# speedPulserPro.net
KiCad netlist of a schematic drawn in EasyEDA Pro
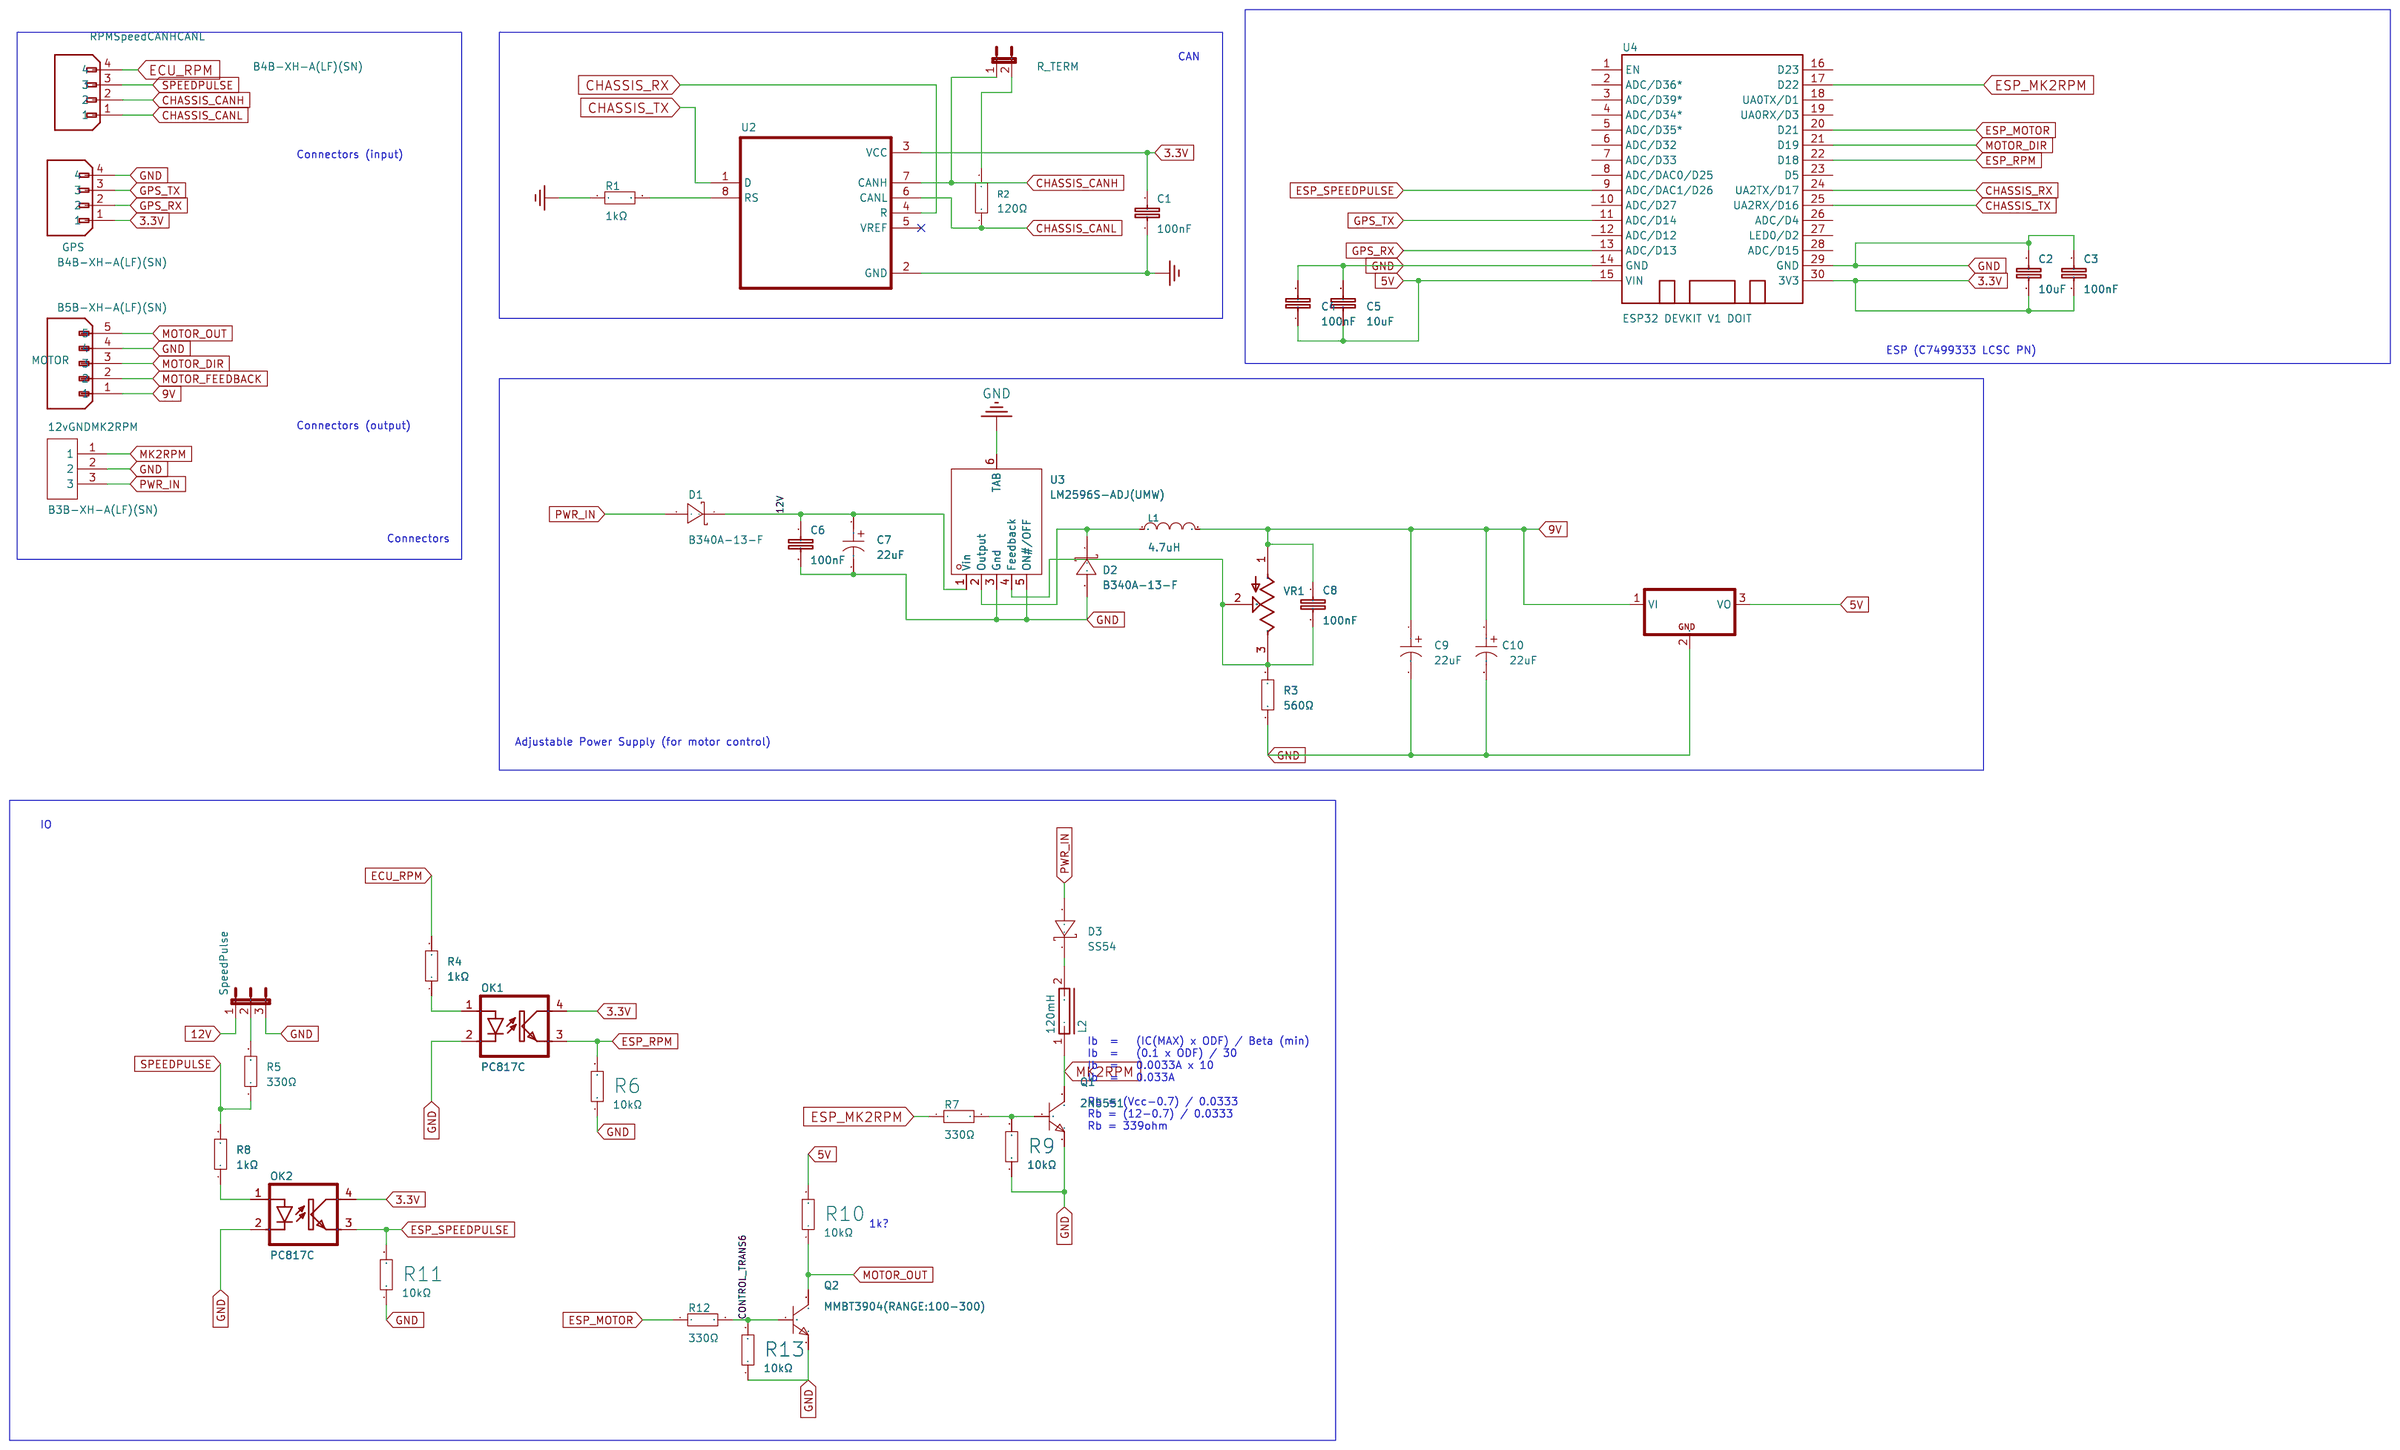
[diagram p0: schematic sheet]

(export (version "E")
  (design (tool "Eeschema 10.0.6"))
  (components
    (comp (ref "12vGNDMK2RPM")
      (value "B3B-XH-A(LF)(SN)")
      (footprint "easyedapro:CONN-TH_3P-P2.50_A2501WV2-3P")
      (fields (field (name "Manufacturer") "JST"))
      (libsource (lib "easyedapro") (part "B3B-XH-A(LF)(SN)"))
    )
    (comp (ref "C1")
      (value "100nF")
      (description "Capacitance:100nF Tolerance:±10% Tolerance:±10% Voltage Rating:50V Temperature Coefficient:X7R")
      (fields
        (field (name "Manufacturer Part") "CC0603KRX7R9BB104")
        (field (name "Manufacturer") "YAGEO(国巨)")
      )
      (libsource (lib "easyedapro") (part "capacitor-wima_C_2.5/2"))
    )
    (comp (ref "C2")
      (value "10uF")
      (fields
        (field (name "Manufacturer Part") "CL21A106KAYNNNE")
        (field (name "Manufacturer") "SAMSUNG(三星)")
      )
      (libsource (lib "easyedapro") (part "capacitor-wima_C_2.5/2"))
    )
    (comp (ref "C3")
      (value "100nF")
      (description "Capacitance:100nF Tolerance:±10% Tolerance:±10% Voltage Rating:50V Temperature Coefficient:X7R")
      (fields
        (field (name "Manufacturer Part") "CC0603KRX7R9BB104")
        (field (name "Manufacturer") "YAGEO(国巨)")
      )
      (libsource (lib "easyedapro") (part "capacitor-wima_C_2.5/2"))
    )
    (comp (ref "C4")
      (value "100nF")
      (description "Capacitance:100nF Tolerance:±10% Tolerance:±10% Voltage Rating:50V Temperature Coefficient:X7R")
      (fields
        (field (name "Manufacturer Part") "CC0603KRX7R9BB104")
        (field (name "Manufacturer") "YAGEO(国巨)")
      )
      (libsource (lib "easyedapro") (part "capacitor-wima_C_2.5/2"))
    )
    (comp (ref "C5")
      (value "10uF")
      (fields
        (field (name "Manufacturer Part") "CL21A106KAYNNNE")
        (field (name "Manufacturer") "SAMSUNG(三星)")
      )
      (libsource (lib "easyedapro") (part "capacitor-wima_C_2.5/2"))
    )
    (comp (ref "C6")
      (value "100nF")
      (description "Capacitance:100nF Tolerance:±10% Tolerance:±10% Voltage Rating:50V Temperature Coefficient:-")
      (fields
        (field (name "Manufacturer Part") "CT41G-0805-2X1-50V-0.1μF-K(N)")
        (field (name "Manufacturer") "TORCH(火炬)")
      )
      (libsource (lib "easyedapro") (part "capacitor-wima_C_2.5/2"))
    )
    (comp (ref "C7")
      (value "22uF")
      (footprint "easyedapro:CAP-SMD_BD5.0-L5.3-W5.3-LS6.3-FD-1")
      (fields (field (name "Manufacturer Part") "RST22UF35V025") (field (name "Manufacturer") "KNSCHA(科尼盛)"))
      (libsource (lib "easyedapro") (part "RST22UF35V025"))
    )
    (comp (ref "C8")
      (value "100nF")
      (description "Capacitance:100nF Tolerance:±10% Tolerance:±10% Voltage Rating:50V Temperature Coefficient:-")
      (fields
        (field (name "Manufacturer Part") "CT41G-0805-2X1-50V-0.1μF-K(N)")
        (field (name "Manufacturer") "TORCH(火炬)")
      )
      (libsource (lib "easyedapro") (part "capacitor-wima_C_2.5/2"))
    )
    (comp (ref "C9")
      (value "22uF")
      (footprint "easyedapro:CAP-SMD_BD5.0-L5.3-W5.3-LS6.3-FD-1")
      (fields (field (name "Manufacturer Part") "RST22UF35V025") (field (name "Manufacturer") "KNSCHA(科尼盛)"))
      (libsource (lib "easyedapro") (part "RST22UF35V025"))
    )
    (comp (ref "C10")
      (value "22uF")
      (footprint "easyedapro:CAP-SMD_BD5.0-L5.3-W5.3-LS6.3-FD-1")
      (fields (field (name "Manufacturer Part") "RST22UF35V025") (field (name "Manufacturer") "KNSCHA(科尼盛)"))
      (libsource (lib "easyedapro") (part "RST22UF35V025"))
    )
    (comp (ref "D1")
      (value "B340A-13-F")
      (footprint "easyedapro:SMA_L4.4-W2.6-LS5.0-RD")
      (fields (field (name "Manufacturer") "DIODES(美台)"))
      (libsource (lib "easyedapro") (part "B340A-13-F"))
    )
    (comp (ref "D2")
      (value "B340A-13-F")
      (footprint "easyedapro:SMA_L4.4-W2.6-LS5.0-RD")
      (fields (field (name "Manufacturer") "DIODES(美台)"))
      (libsource (lib "easyedapro") (part "B340A-13-F"))
    )
    (comp (ref "D3")
      (value "SS54")
      (footprint "easyedapro:SMA_L4.4-W2.8-LS5.4-R-RD")
      (fields (field (name "Manufacturer") "MDD(辰达半导体)"))
      (libsource (lib "easyedapro") (part "SS54_C22452"))
    )
    (comp (ref "GPS")
      (value "B4B-XH-A(LF)(SN)")
      (fields (field (name "Manufacturer") "JST"))
      (libsource (lib "easyedapro") (part "B4B-XH-A_LF__SN__B4B-XH-A(LF)(SN)_"))
    )
    (comp (ref "IC1")
      (value "L7805ABD2T-TR")
      (fields (field (name "Manufacturer") "ST(意法半导体)"))
      (libsource (lib "easyedapro") (part "linear_78*_TV"))
    )
    (comp (ref "L1")
      (value "4.7uH")
      (footprint "easyedapro:IND-SMD_L4.8-W4.5")
      (fields (field (name "Manufacturer Part") "SMMS0420-4R7M") (field (name "Manufacturer") "SXN(顺翔诺)"))
      (libsource (lib "easyedapro") (part "SMMS0420-4R7M"))
    )
    (comp (ref "L2")
      (value "120mH")
      (fields (field (name "Manufacturer Part") "DR125-124-R") (field (name "Manufacturer") "EATON(伊顿)"))
      (libsource (lib "easyedapro") (part "DR125_DR125_"))
    )
    (comp (ref "MOTOR")
      (value "B5B-XH-A(LF)(SN)")
      (fields (field (name "Manufacturer") "JST"))
      (libsource (lib "easyedapro") (part "B5B-XH-A_LF__SN__B5B-XH-A(LF)(SN)_"))
    )
    (comp (ref "OK1")
      (value "PC817C")
      (fields (field (name "Manufacturer") "GOODWORK(固得沃克)"))
      (libsource (lib "easyedapro") (part "optocoupler_PC817_"))
    )
    (comp (ref "OK2")
      (value "PC817C")
      (fields (field (name "Manufacturer") "GOODWORK(固得沃克)"))
      (libsource (lib "easyedapro") (part "optocoupler_PC817_"))
    )
    (comp (ref "Q1")
      (value "2N5551")
      (footprint "easyedapro:SOT-23-3_L2.9-W1.4-P1.90-LS2.5-BR")
      (fields (field (name "Manufacturer") "RUILON(瑞隆源)"))
      (libsource (lib "easyedapro") (part "2N5551_C7529570"))
    )
    (comp (ref "Q2")
      (value "MMBT3904(RANGE:100-300)")
      (footprint "easyedapro:SOT-23-3_L2.9-W1.3-P1.90-LS2.4-BR")
      (fields (field (name "Manufacturer") "CJ(江苏长电/长晶)"))
      (libsource (lib "easyedapro") (part "MMBT3904"))
    )
    (comp (ref "R1")
      (value "1kΩ")
      (footprint "easyedapro:R0603")
      (fields
        (field (name "Manufacturer Part") "0603WAF1001T5E")
        (field (name "Manufacturer") "UNI-ROYAL(厚声)")
      )
      (libsource (lib "easyedapro") (part "0603WAF1001T5E"))
    )
    (comp (ref "R2")
      (value "120Ω")
      (footprint "easyedapro:R0603")
      (fields
        (field (name "Manufacturer Part") "0603WAF1200T5E")
        (field (name "Manufacturer") "UNI-ROYAL(厚声)")
      )
      (libsource (lib "easyedapro") (part "0603WAF1200T5E"))
    )
    (comp (ref "R3")
      (value "560Ω")
      (footprint "easyedapro:R0603")
      (fields
        (field (name "Manufacturer Part") "0603WAF5600T5E")
        (field (name "Manufacturer") "UNI-ROYAL(厚声)")
      )
      (libsource (lib "easyedapro") (part "0603WAF5600T5E"))
    )
    (comp (ref "R4")
      (value "1kΩ")
      (footprint "easyedapro:R0603")
      (fields
        (field (name "Manufacturer Part") "0603WAF1001T5E")
        (field (name "Manufacturer") "UNI-ROYAL(厚声)")
      )
      (libsource (lib "easyedapro") (part "0603WAF1001T5E"))
    )
    (comp (ref "R5")
      (value "330Ω")
      (footprint "easyedapro:R0603")
      (fields
        (field (name "Manufacturer Part") "0603WAF3300T5E")
        (field (name "Manufacturer") "UNI-ROYAL(厚声)")
      )
      (libsource (lib "easyedapro") (part "0603WAF3300T5E"))
    )
    (comp (ref "R6")
      (value "10kΩ")
      (footprint "easyedapro:R0603")
      (fields
        (field (name "Manufacturer Part") "0603WAF1002T5E")
        (field (name "Manufacturer") "UNI-ROYAL(厚声)")
      )
      (libsource (lib "easyedapro") (part "0603WAF1002T5E"))
    )
    (comp (ref "R7")
      (value "330Ω")
      (footprint "easyedapro:R0603")
      (fields
        (field (name "Manufacturer Part") "0603WAF3300T5E")
        (field (name "Manufacturer") "UNI-ROYAL(厚声)")
      )
      (libsource (lib "easyedapro") (part "0603WAF3300T5E"))
    )
    (comp (ref "R8")
      (value "1kΩ")
      (footprint "easyedapro:R0603")
      (fields
        (field (name "Manufacturer Part") "0603WAF1001T5E")
        (field (name "Manufacturer") "UNI-ROYAL(厚声)")
      )
      (libsource (lib "easyedapro") (part "0603WAF1001T5E"))
    )
    (comp (ref "R9")
      (value "10kΩ")
      (footprint "easyedapro:R0603")
      (fields
        (field (name "Manufacturer Part") "0603WAF1002T5E")
        (field (name "Manufacturer") "UNI-ROYAL(厚声)")
      )
      (libsource (lib "easyedapro") (part "0603WAF1002T5E"))
    )
    (comp (ref "R10")
      (value "10kΩ")
      (footprint "easyedapro:R0603")
      (fields
        (field (name "Manufacturer Part") "0603WAF1002T5E")
        (field (name "Manufacturer") "UNI-ROYAL(厚声)")
      )
      (libsource (lib "easyedapro") (part "0603WAF1002T5E"))
    )
    (comp (ref "R11")
      (value "10kΩ")
      (footprint "easyedapro:R0603")
      (fields
        (field (name "Manufacturer Part") "0603WAF1002T5E")
        (field (name "Manufacturer") "UNI-ROYAL(厚声)")
      )
      (libsource (lib "easyedapro") (part "0603WAF1002T5E"))
    )
    (comp (ref "R12")
      (value "330Ω")
      (footprint "easyedapro:R0603")
      (fields
        (field (name "Manufacturer Part") "0603WAF3300T5E")
        (field (name "Manufacturer") "UNI-ROYAL(厚声)")
      )
      (libsource (lib "easyedapro") (part "0603WAF3300T5E"))
    )
    (comp (ref "R13")
      (value "10kΩ")
      (footprint "easyedapro:R0603")
      (fields
        (field (name "Manufacturer Part") "0603WAF1002T5E")
        (field (name "Manufacturer") "UNI-ROYAL(厚声)")
      )
      (libsource (lib "easyedapro") (part "0603WAF1002T5E"))
    )
    (comp (ref "RPMSpeedCANHCANL")
      (value "B4B-XH-A(LF)(SN)")
      (fields (field (name "Manufacturer") "JST"))
      (libsource (lib "easyedapro") (part "B4B-XH-A_LF__SN__B4B-XH-A(LF)(SN)_"))
    )
    (comp (ref "R_TERM")
      (value "PZ254V-11-02P")
      (fields (field (name "Manufacturer") "XFCN(兴飞)"))
      (libsource (lib "easyedapro") (part "jumper_JP1E_"))
    )
    (comp (ref "SpeedPulse")
      (value "PZ254V-11-03P")
      (fields (field (name "Manufacturer") "XFCN(兴飞)"))
      (libsource (lib "easyedapro") (part "jumper_JP2E_"))
    )
    (comp (ref "U2")
      (value "SN65HVD230DR")
      (fields (field (name "Manufacturer") "TI(德州仪器)"))
      (libsource (lib "easyedapro") (part "SN65HVD230DR_SN65HVD230DR_"))
    )
    (comp (ref "U3")
      (value "LM2596S-ADJ(UMW)")
      (footprint "easyedapro:TO-263-5_L10.2-W8.9-P1.70-BR")
      (fields (field (name "Manufacturer") "UMW(友台半导体)"))
      (libsource (lib "easyedapro") (part "LM2596S-ADJ"))
    )
    (comp (ref "U4")
      (value "ESP32 DEVKIT V1 DOIT")
      (footprint "easyedapro:DOIT-ESP32-DEVKIT-V1")
      (libsource (lib "easyedapro") (part "ESP32 DEVKIT V1 DOIT"))
    )
    (comp (ref "VR1")
      (value "10kΩ")
      (description "Resistance: Tolerance:±10% Tolerance:±10%")
      (fields (field (name "Manufacturer Part") "3362P-1-103") (field (name "Manufacturer") "BOCHEN(博晨)"))
      (libsource (lib "easyedapro") (part "3362P-1-253LF_3362P-1-253LF_"))
    )
  )
  (nets
    (net (code "1") (name "/CONTROL_TRANS6") (class "Default")
      (node (ref "Q2") (pin "1") (pinfunction "B_1") (pintype "unspecified"))
      (node (ref "R12") (pin "2") (pinfunction "2_2") (pintype "input"))
      (node (ref "R13") (pin "2") (pinfunction "2_2") (pintype "input"))
    )
    (net (code "2") (name "3.3V") (class "Default")
      (node (ref "C1") (pin "1") (pinfunction "1_1") (pintype "unspecified"))
      (node (ref "C2") (pin "2") (pinfunction "2_2") (pintype "unspecified"))
      (node (ref "C3") (pin "2") (pinfunction "2_2") (pintype "unspecified"))
      (node (ref "GPS") (pin "1") (pinfunction "1_1") (pintype "unspecified"))
      (node (ref "OK1") (pin "4") (pinfunction "COL_4") (pintype "unspecified"))
      (node (ref "OK2") (pin "4") (pinfunction "COL_4") (pintype "unspecified"))
      (node (ref "U2") (pin "3") (pinfunction "VCC_3") (pintype "unspecified"))
      (node (ref "U4") (pin "30") (pinfunction "3V3_30") (pintype "bidirectional"))
    )
    (net (code "3") (name "5V") (class "Default")
      (node (ref "C4") (pin "1") (pinfunction "1_1") (pintype "unspecified"))
      (node (ref "C5") (pin "1") (pinfunction "1_1") (pintype "unspecified"))
      (node (ref "IC1") (pin "3") (pinfunction "VO_3") (pintype "unspecified"))
      (node (ref "R10") (pin "2") (pinfunction "2_2") (pintype "input"))
      (node (ref "U4") (pin "15") (pinfunction "VIN_15") (pintype "input"))
    )
    (net (code "4") (name "9V") (class "Default")
      (node (ref "C10") (pin "1") (pinfunction "1_1") (pintype "input"))
      (node (ref "C8") (pin "1") (pinfunction "1_1") (pintype "unspecified"))
      (node (ref "C9") (pin "1") (pinfunction "1_1") (pintype "input"))
      (node (ref "IC1") (pin "1") (pinfunction "VI_1") (pintype "input"))
      (node (ref "L1") (pin "2") (pinfunction "2_2") (pintype "input"))
      (node (ref "MOTOR") (pin "1") (pinfunction "1_1") (pintype "unspecified"))
      (node (ref "VR1") (pin "1") (pinfunction "CCW_1") (pintype "unspecified"))
    )
    (net (code "5") (name "12V") (class "Default")
      (node (ref "C6") (pin "1") (pinfunction "1_1") (pintype "unspecified"))
      (node (ref "C7") (pin "1") (pinfunction "1_1") (pintype "input"))
      (node (ref "D1") (pin "1") (pinfunction "K_1") (pintype "unspecified"))
      (node (ref "SpeedPulse") (pin "1") (pinfunction "1_1") (pintype "unspecified"))
      (node (ref "U3") (pin "1") (pinfunction "Vin_1") (pintype "unspecified"))
    )
    (net (code "6") (name "CHASSIS_CANH") (class "Default")
      (node (ref "RPMSpeedCANHCANL") (pin "2") (pinfunction "2_2") (pintype "unspecified"))
      (node (ref "R_TERM") (pin "1") (pinfunction "1_1") (pintype "unspecified"))
      (node (ref "U2") (pin "7") (pinfunction "CANH_7") (pintype "output"))
    )
    (net (code "7") (name "CHASSIS_CANL") (class "Default")
      (node (ref "R2") (pin "1") (pinfunction "1_1") (pintype "input"))
      (node (ref "RPMSpeedCANHCANL") (pin "1") (pinfunction "1_1") (pintype "unspecified"))
      (node (ref "U2") (pin "6") (pinfunction "CANL_6") (pintype "output"))
    )
    (net (code "8") (name "CHASSIS_RX") (class "Default")
      (node (ref "U2") (pin "4") (pinfunction "R_4") (pintype "output"))
      (node (ref "U4") (pin "24") (pinfunction "UA2TX/D17_24") (pintype "bidirectional"))
    )
    (net (code "9") (name "CHASSIS_TX") (class "Default")
      (node (ref "U2") (pin "1") (pinfunction "D_1") (pintype "input"))
      (node (ref "U4") (pin "25") (pinfunction "UA2RX/D16_25") (pintype "bidirectional"))
    )
    (net (code "10") (name "ECU_RPM") (class "Default")
      (node (ref "R4") (pin "2") (pinfunction "2_2") (pintype "input"))
      (node (ref "RPMSpeedCANHCANL") (pin "4") (pinfunction "4_4") (pintype "unspecified"))
    )
    (net (code "11") (name "ESP_MK2RPM") (class "Default")
      (node (ref "R7") (pin "1") (pinfunction "1_1") (pintype "input"))
      (node (ref "U4") (pin "17") (pinfunction "D22_17") (pintype "bidirectional"))
    )
    (net (code "12") (name "ESP_MOTOR") (class "Default")
      (node (ref "R12") (pin "1") (pinfunction "1_1") (pintype "input"))
      (node (ref "U4") (pin "20") (pinfunction "D21_20") (pintype "bidirectional"))
    )
    (net (code "13") (name "ESP_RPM") (class "Default")
      (node (ref "OK1") (pin "3") (pinfunction "EMIT_3") (pintype "unspecified"))
      (node (ref "R6") (pin "2") (pinfunction "2_2") (pintype "input"))
      (node (ref "U4") (pin "22") (pinfunction "D18_22") (pintype "bidirectional"))
    )
    (net (code "14") (name "ESP_SPEEDPULSE") (class "Default")
      (node (ref "OK2") (pin "3") (pinfunction "EMIT_3") (pintype "unspecified"))
      (node (ref "R11") (pin "2") (pinfunction "2_2") (pintype "input"))
      (node (ref "U4") (pin "9") (pinfunction "ADC/DAC1/D26_9") (pintype "bidirectional"))
    )
    (net (code "15") (name "GND") (class "Default")
      (node (ref "12vGNDMK2RPM") (pin "2") (pinfunction "2_2") (pintype "unspecified"))
      (node (ref "C1") (pin "2") (pinfunction "2_2") (pintype "unspecified"))
      (node (ref "C10") (pin "2") (pinfunction "2_2") (pintype "input"))
      (node (ref "C2") (pin "1") (pinfunction "1_1") (pintype "unspecified"))
      (node (ref "C3") (pin "1") (pinfunction "1_1") (pintype "unspecified"))
      (node (ref "C4") (pin "2") (pinfunction "2_2") (pintype "unspecified"))
      (node (ref "C5") (pin "2") (pinfunction "2_2") (pintype "unspecified"))
      (node (ref "C6") (pin "2") (pinfunction "2_2") (pintype "unspecified"))
      (node (ref "C7") (pin "2") (pinfunction "2_2") (pintype "input"))
      (node (ref "C9") (pin "2") (pinfunction "2_2") (pintype "input"))
      (node (ref "D2") (pin "2") (pinfunction "A_2") (pintype "unspecified"))
      (node (ref "GPS") (pin "4") (pinfunction "4_4") (pintype "unspecified"))
      (node (ref "IC1") (pin "2") (pinfunction "GND_2") (pintype "unspecified"))
      (node (ref "MOTOR") (pin "4") (pinfunction "4_4") (pintype "unspecified"))
      (node (ref "OK1") (pin "2") (pinfunction "C_2") (pintype "unspecified"))
      (node (ref "OK2") (pin "2") (pinfunction "C_2") (pintype "unspecified"))
      (node (ref "Q1") (pin "2") (pinfunction "E_2") (pintype "unspecified"))
      (node (ref "Q2") (pin "2") (pinfunction "E_2") (pintype "unspecified"))
      (node (ref "R1") (pin "1") (pinfunction "1_1") (pintype "input"))
      (node (ref "R11") (pin "1") (pinfunction "1_1") (pintype "input"))
      (node (ref "R13") (pin "1") (pinfunction "1_1") (pintype "input"))
      (node (ref "R3") (pin "1") (pinfunction "1_1") (pintype "input"))
      (node (ref "R6") (pin "1") (pinfunction "1_1") (pintype "input"))
      (node (ref "R9") (pin "1") (pinfunction "1_1") (pintype "input"))
      (node (ref "SpeedPulse") (pin "3") (pinfunction "3_3") (pintype "unspecified"))
      (node (ref "U2") (pin "2") (pinfunction "GND_2") (pintype "unspecified"))
      (node (ref "U3") (pin "3") (pinfunction "Gnd_3") (pintype "unspecified"))
      (node (ref "U3") (pin "5") (pinfunction "ON#/OFF_5") (pintype "unspecified"))
      (node (ref "U3") (pin "6") (pinfunction "TAB_6") (pintype "unspecified"))
      (node (ref "U4") (pin "14") (pinfunction "GND_14") (pintype "bidirectional"))
      (node (ref "U4") (pin "29") (pinfunction "GND_29") (pintype "bidirectional"))
    )
    (net (code "16") (name "GPS_RX") (class "Default")
      (node (ref "GPS") (pin "2") (pinfunction "2_2") (pintype "unspecified"))
      (node (ref "U4") (pin "13") (pinfunction "ADC/D13_13") (pintype "bidirectional"))
    )
    (net (code "17") (name "GPS_TX") (class "Default")
      (node (ref "GPS") (pin "3") (pinfunction "3_3") (pintype "unspecified"))
      (node (ref "U4") (pin "11") (pinfunction "ADC/D14_11") (pintype "bidirectional"))
    )
    (net (code "18") (name "MK2RPM") (class "Default")
      (node (ref "12vGNDMK2RPM") (pin "1") (pinfunction "1_1") (pintype "unspecified"))
      (node (ref "L2") (pin "1") (pinfunction "1_1") (pintype "unspecified"))
      (node (ref "Q1") (pin "3") (pinfunction "C_3") (pintype "unspecified"))
    )
    (net (code "19") (name "MOTOR_DIR") (class "Default")
      (node (ref "MOTOR") (pin "3") (pinfunction "3_3") (pintype "unspecified"))
      (node (ref "U4") (pin "21") (pinfunction "D19_21") (pintype "bidirectional"))
    )
    (net (code "20") (name "MOTOR_FEEDBACK") (class "Default")
      (node (ref "MOTOR") (pin "2") (pinfunction "2_2") (pintype "unspecified"))
    )
    (net (code "21") (name "MOTOR_OUT") (class "Default")
      (node (ref "MOTOR") (pin "5") (pinfunction "5_5") (pintype "unspecified"))
      (node (ref "Q2") (pin "3") (pinfunction "C_3") (pintype "unspecified"))
      (node (ref "R10") (pin "1") (pinfunction "1_1") (pintype "input"))
    )
    (net (code "22") (name "Net-(D2-K)") (class "Default")
      (node (ref "D2") (pin "1") (pinfunction "K_1") (pintype "unspecified"))
      (node (ref "L1") (pin "1") (pinfunction "1_1") (pintype "input"))
      (node (ref "U3") (pin "2") (pinfunction "Output_2") (pintype "unspecified"))
    )
    (net (code "23") (name "Net-(D3-K)") (class "Default")
      (node (ref "D3") (pin "2") (pinfunction "K_2") (pintype "unspecified"))
      (node (ref "L2") (pin "2") (pinfunction "2_2") (pintype "unspecified"))
    )
    (net (code "24") (name "Net-(OK1-A)") (class "Default")
      (node (ref "OK1") (pin "1") (pinfunction "A_1") (pintype "unspecified"))
      (node (ref "R4") (pin "1") (pinfunction "1_1") (pintype "input"))
    )
    (net (code "25") (name "Net-(OK2-A)") (class "Default")
      (node (ref "OK2") (pin "1") (pinfunction "A_1") (pintype "unspecified"))
      (node (ref "R8") (pin "1") (pinfunction "1_1") (pintype "input"))
    )
    (net (code "26") (name "Net-(Q1-B)") (class "Default")
      (node (ref "Q1") (pin "1") (pinfunction "B_1") (pintype "unspecified"))
      (node (ref "R7") (pin "2") (pinfunction "2_2") (pintype "input"))
      (node (ref "R9") (pin "2") (pinfunction "2_2") (pintype "input"))
    )
    (net (code "27") (name "Net-(R2-Pad2)") (class "Default")
      (node (ref "R2") (pin "2") (pinfunction "2_2") (pintype "input"))
      (node (ref "R_TERM") (pin "2") (pinfunction "2_2") (pintype "unspecified"))
    )
    (net (code "28") (name "Net-(R5-Pad2)") (class "Default")
      (node (ref "R5") (pin "2") (pinfunction "2_2") (pintype "input"))
      (node (ref "SpeedPulse") (pin "2") (pinfunction "2_2") (pintype "unspecified"))
    )
    (net (code "29") (name "Net-(U2-RS)") (class "Default")
      (node (ref "R1") (pin "2") (pinfunction "2_2") (pintype "input"))
      (node (ref "U2") (pin "8") (pinfunction "RS_8") (pintype "input"))
    )
    (net (code "30") (name "Net-(U3-Feedback)") (class "Default")
      (node (ref "C8") (pin "2") (pinfunction "2_2") (pintype "unspecified"))
      (node (ref "R3") (pin "2") (pinfunction "2_2") (pintype "input"))
      (node (ref "U3") (pin "4") (pinfunction "Feedback_4") (pintype "unspecified"))
      (node (ref "VR1") (pin "2") (pinfunction "WIPER_2") (pintype "unspecified"))
      (node (ref "VR1") (pin "3") (pinfunction "CW_3") (pintype "unspecified"))
    )
    (net (code "31") (name "PWR_IN") (class "Default")
      (node (ref "12vGNDMK2RPM") (pin "3") (pinfunction "3_3") (pintype "unspecified"))
      (node (ref "D1") (pin "2") (pinfunction "A_2") (pintype "unspecified"))
      (node (ref "D3") (pin "1") (pinfunction "A_1") (pintype "unspecified"))
    )
    (net (code "32") (name "SPEEDPULSE") (class "Default")
      (node (ref "R5") (pin "1") (pinfunction "1_1") (pintype "input"))
      (node (ref "R8") (pin "2") (pinfunction "2_2") (pintype "input"))
      (node (ref "RPMSpeedCANHCANL") (pin "3") (pinfunction "3_3") (pintype "unspecified"))
    )
    (net (code "33") (name "unconnected-(U2-VREF-Pad5)") (class "Default")
      (node (ref "U2") (pin "5") (pinfunction "VREF_5") (pintype "output+no_connect"))
    )
    (net (code "34") (name "unconnected-(U4-ADC{slash}D4-Pad26)") (class "Default")
      (node (ref "U4") (pin "26") (pinfunction "ADC/D4_26") (pintype "bidirectional"))
    )
    (net (code "35") (name "unconnected-(U4-ADC{slash}D12-Pad12)") (class "Default")
      (node (ref "U4") (pin "12") (pinfunction "ADC/D12_12") (pintype "bidirectional"))
    )
    (net (code "36") (name "unconnected-(U4-ADC{slash}D15-Pad28)") (class "Default")
      (node (ref "U4") (pin "28") (pinfunction "ADC/D15_28") (pintype "bidirectional"))
    )
    (net (code "37") (name "unconnected-(U4-ADC{slash}D27-Pad10)") (class "Default")
      (node (ref "U4") (pin "10") (pinfunction "ADC/D27_10") (pintype "bidirectional"))
    )
    (net (code "38") (name "unconnected-(U4-ADC{slash}D32-Pad6)") (class "Default")
      (node (ref "U4") (pin "6") (pinfunction "ADC/D32_6") (pintype "bidirectional"))
    )
    (net (code "39") (name "unconnected-(U4-ADC{slash}D33-Pad7)") (class "Default")
      (node (ref "U4") (pin "7") (pinfunction "ADC/D33_7") (pintype "bidirectional"))
    )
    (net (code "40") (name "unconnected-(U4-ADC{slash}D34*-Pad4)") (class "Default")
      (node (ref "U4") (pin "4") (pinfunction "ADC/D34*_4") (pintype "input"))
    )
    (net (code "41") (name "unconnected-(U4-ADC{slash}D35*-Pad5)") (class "Default")
      (node (ref "U4") (pin "5") (pinfunction "ADC/D35*_5") (pintype "input"))
    )
    (net (code "42") (name "unconnected-(U4-ADC{slash}D36*-Pad2)") (class "Default")
      (node (ref "U4") (pin "2") (pinfunction "ADC/D36*_2") (pintype "input"))
    )
    (net (code "43") (name "unconnected-(U4-ADC{slash}D39*-Pad3)") (class "Default")
      (node (ref "U4") (pin "3") (pinfunction "ADC/D39*_3") (pintype "input"))
    )
    (net (code "44") (name "unconnected-(U4-ADC{slash}DAC0{slash}D25-Pad8)") (class "Default")
      (node (ref "U4") (pin "8") (pinfunction "ADC/DAC0/D25_8") (pintype "bidirectional"))
    )
    (net (code "45") (name "unconnected-(U4-D5-Pad23)") (class "Default")
      (node (ref "U4") (pin "23") (pinfunction "D5_23") (pintype "bidirectional"))
    )
    (net (code "46") (name "unconnected-(U4-D23-Pad16)") (class "Default")
      (node (ref "U4") (pin "16") (pinfunction "D23_16") (pintype "bidirectional"))
    )
    (net (code "47") (name "unconnected-(U4-EN-Pad1)") (class "Default")
      (node (ref "U4") (pin "1") (pinfunction "EN_1") (pintype "bidirectional"))
    )
    (net (code "48") (name "unconnected-(U4-LED0{slash}D2-Pad27)") (class "Default")
      (node (ref "U4") (pin "27") (pinfunction "LED0/D2_27") (pintype "bidirectional"))
    )
    (net (code "49") (name "unconnected-(U4-UA0RX{slash}D3-Pad19)") (class "Default")
      (node (ref "U4") (pin "19") (pinfunction "UA0RX/D3_19") (pintype "bidirectional"))
    )
    (net (code "50") (name "unconnected-(U4-UA0TX{slash}D1-Pad18)") (class "Default")
      (node (ref "U4") (pin "18") (pinfunction "UA0TX/D1_18") (pintype "bidirectional"))
    )
  )
)
